# main.net
KiCad netlist of a schematic drawn in EAGLE
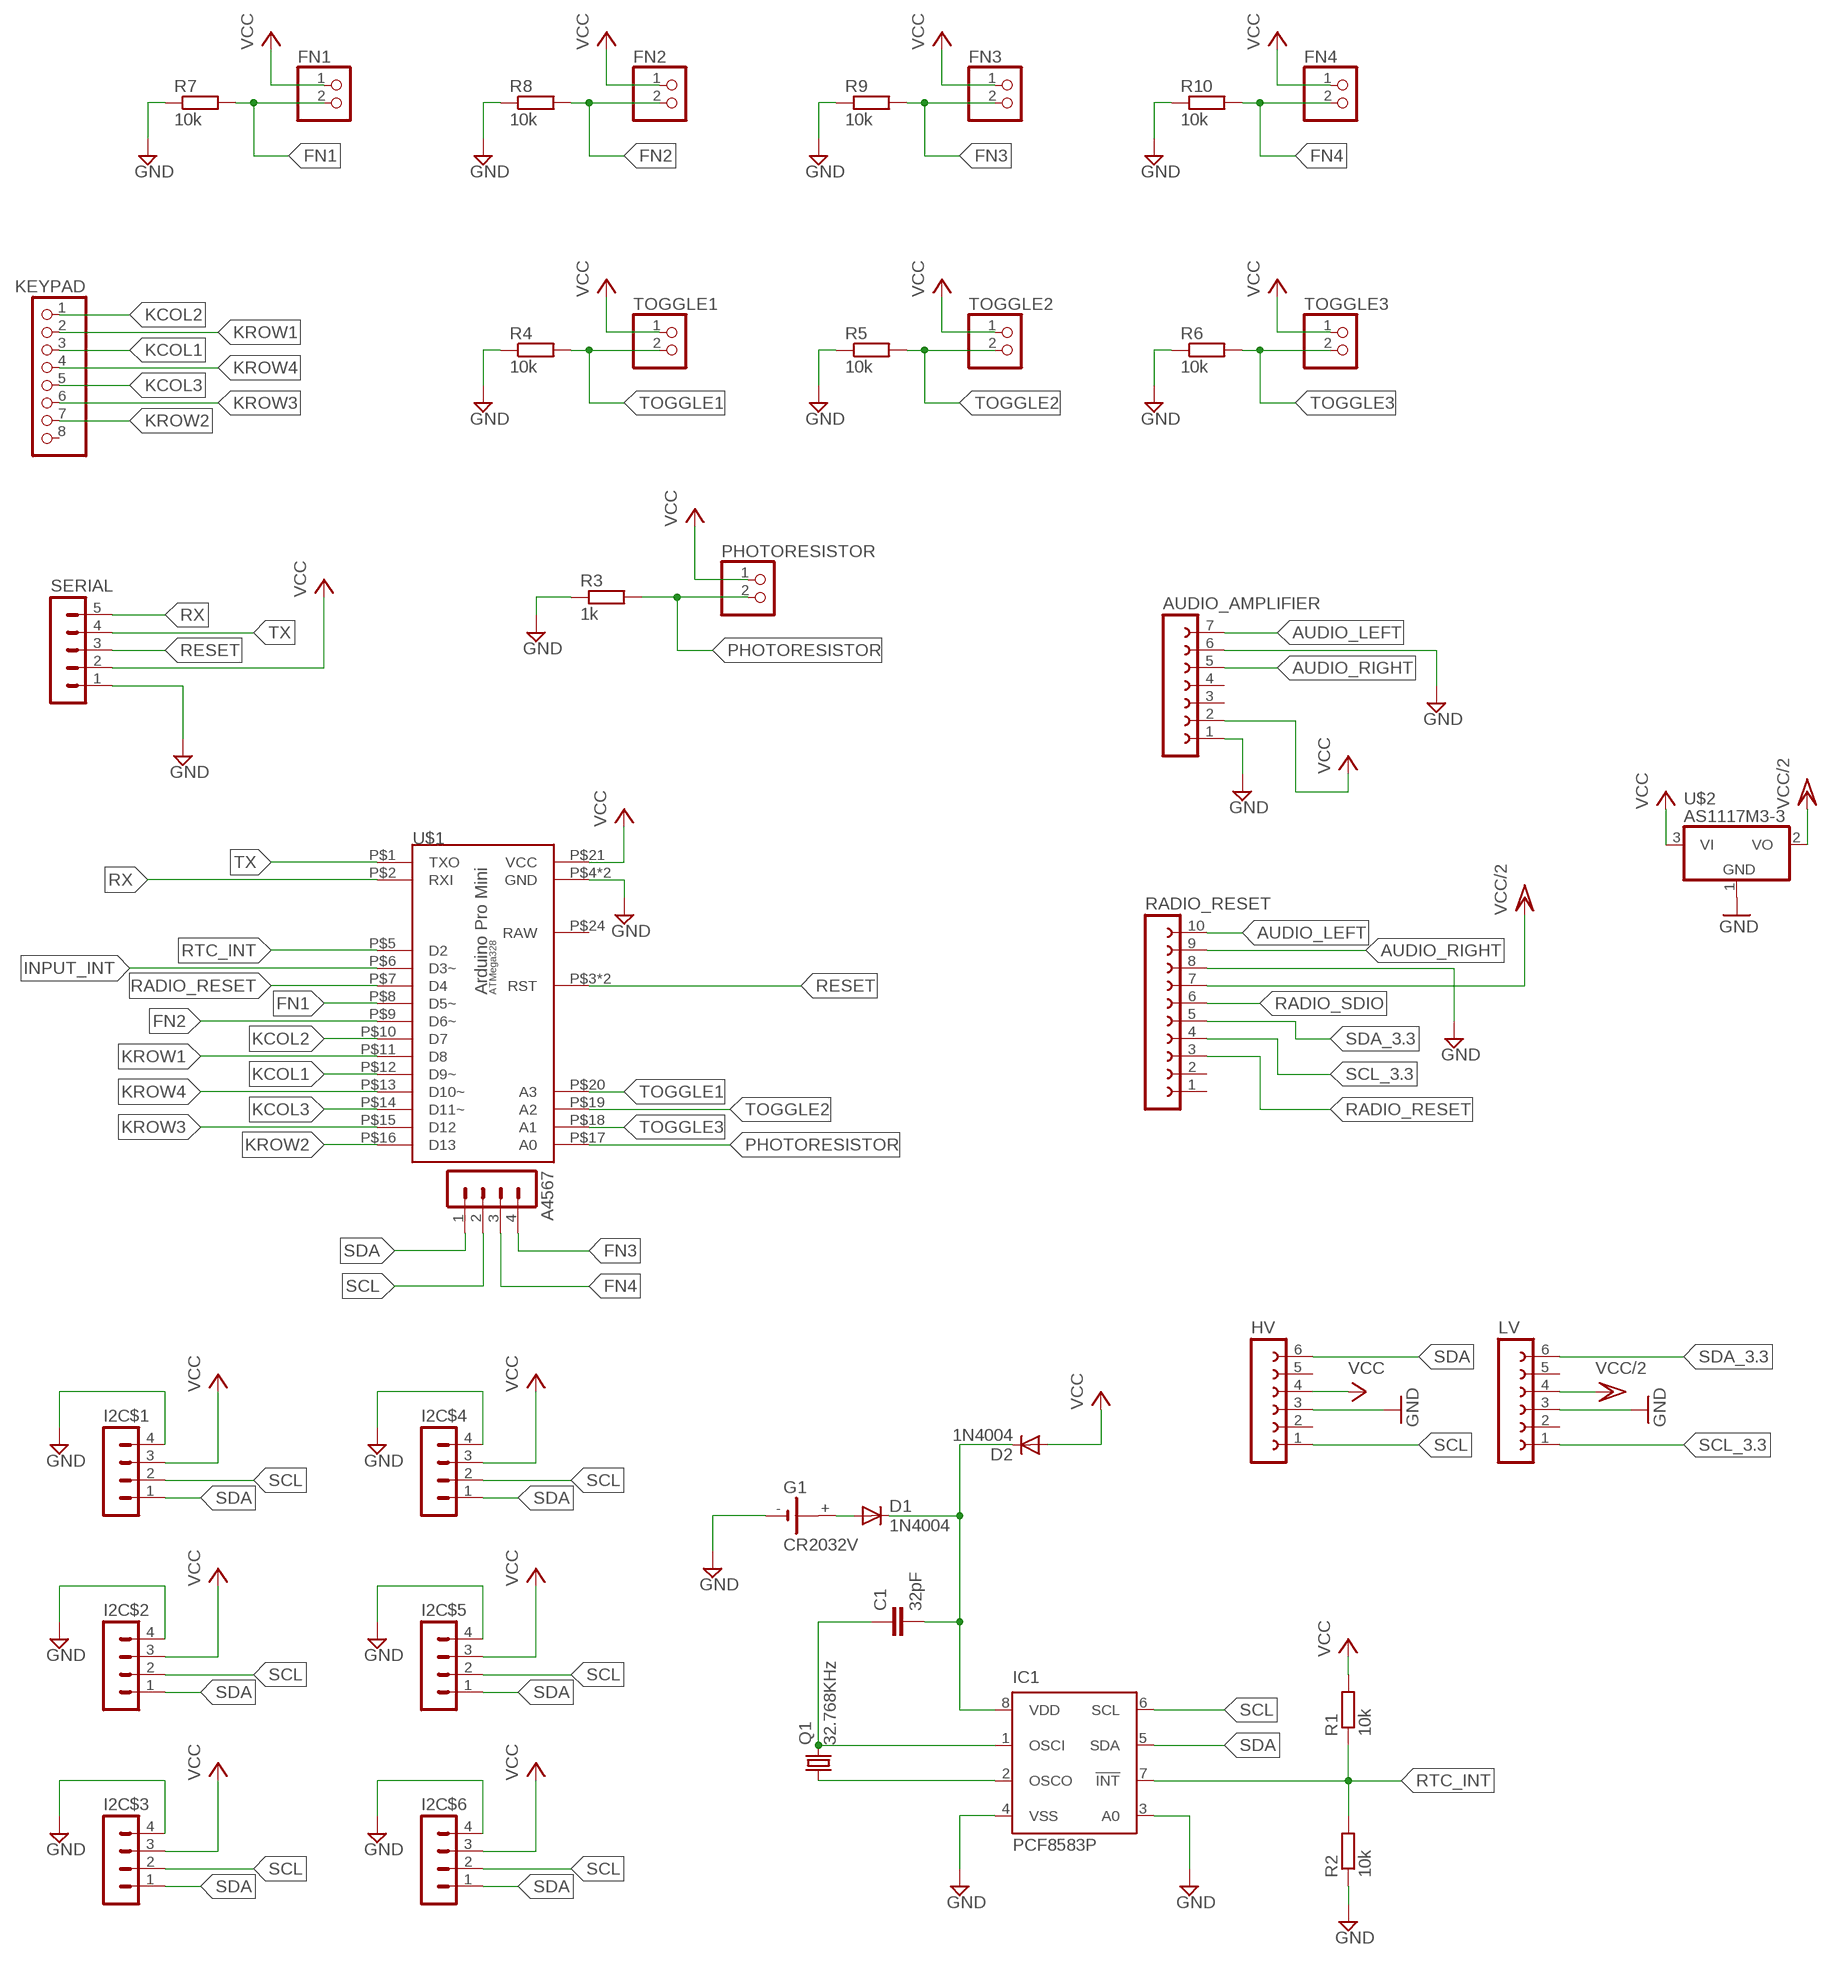
[diagram p0: schematic, sheet 1]

(export (version "E")
  (design (tool "Eeschema 10.0.6"))
  (components
    (comp (ref "A4567")
      (value "MA04-1")
      (footprint "eagle-import:MA04-1")
      (libsource (lib "eagle-import") (part "MA04-1"))
    )
    (comp (ref "AUDIO_AMPLIFIER")
      (value "FE07-1")
      (footprint "eagle-import:FE07")
      (libsource (lib "eagle-import") (part "FE07-1"))
    )
    (comp (ref "C1")
      (value "32pF")
      (footprint "eagle-import:C025-024X044")
      (libsource (lib "eagle-import") (part "C-EU025-024X044"))
    )
    (comp (ref "D1")
      (value "1N4004")
      (footprint "eagle-import:DO41-10")
      (libsource (lib "eagle-import") (part "1N4004"))
    )
    (comp (ref "D2")
      (value "1N4004")
      (footprint "eagle-import:DO41-10")
      (libsource (lib "eagle-import") (part "1N4004"))
    )
    (comp (ref "FN1")
      (value "PINHD-1X2")
      (footprint "eagle-import:1X02")
      (libsource (lib "eagle-import") (part "PINHD-1X2"))
    )
    (comp (ref "FN2")
      (value "PINHD-1X2")
      (footprint "eagle-import:1X02")
      (libsource (lib "eagle-import") (part "PINHD-1X2"))
    )
    (comp (ref "FN3")
      (value "PINHD-1X2")
      (footprint "eagle-import:1X02")
      (libsource (lib "eagle-import") (part "PINHD-1X2"))
    )
    (comp (ref "FN4")
      (value "PINHD-1X2")
      (footprint "eagle-import:1X02")
      (libsource (lib "eagle-import") (part "PINHD-1X2"))
    )
    (comp (ref "G1")
      (value "CR2032V")
      (footprint "eagle-import:CR2032V")
      (libsource (lib "eagle-import") (part "CR2032V"))
    )
    (comp (ref "HV")
      (value "FE06-1")
      (footprint "eagle-import:FE06")
      (libsource (lib "eagle-import") (part "FE06-1"))
    )
    (comp (ref "I2C$1")
      (value "MA04-1")
      (footprint "eagle-import:MA04-1")
      (libsource (lib "eagle-import") (part "MA04-1"))
    )
    (comp (ref "I2C$2")
      (value "MA04-1")
      (footprint "eagle-import:MA04-1")
      (libsource (lib "eagle-import") (part "MA04-1"))
    )
    (comp (ref "I2C$3")
      (value "MA04-1")
      (footprint "eagle-import:MA04-1")
      (libsource (lib "eagle-import") (part "MA04-1"))
    )
    (comp (ref "I2C$4")
      (value "MA04-1")
      (footprint "eagle-import:MA04-1")
      (libsource (lib "eagle-import") (part "MA04-1"))
    )
    (comp (ref "I2C$5")
      (value "MA04-1")
      (footprint "eagle-import:MA04-1")
      (libsource (lib "eagle-import") (part "MA04-1"))
    )
    (comp (ref "I2C$6")
      (value "MA04-1")
      (footprint "eagle-import:MA04-1")
      (libsource (lib "eagle-import") (part "MA04-1"))
    )
    (comp (ref "IC1")
      (value "PCF8583P")
      (footprint "eagle-import:DIL08")
      (libsource (lib "eagle-import") (part "PCF8583P"))
    )
    (comp (ref "KEYPAD")
      (value "PINHD-1X8")
      (footprint "eagle-import:1X08")
      (libsource (lib "eagle-import") (part "PINHD-1X8"))
    )
    (comp (ref "LV")
      (value "FE06-1")
      (footprint "eagle-import:FE06")
      (libsource (lib "eagle-import") (part "FE06-1"))
    )
    (comp (ref "PHOTORESISTOR")
      (value "PINHD-1X2")
      (footprint "eagle-import:1X02")
      (libsource (lib "eagle-import") (part "PINHD-1X2"))
    )
    (comp (ref "Q1")
      (value "32.768KHz")
      (footprint "eagle-import:TC26H")
      (libsource (lib "eagle-import") (part "CRYSTALTC26H"))
    )
    (comp (ref "R1")
      (value "10k")
      (footprint "eagle-import:M0805")
      (libsource (lib "eagle-import") (part "resistor_R-EU_M0805"))
    )
    (comp (ref "R2")
      (value "10k")
      (footprint "eagle-import:M0805")
      (libsource (lib "eagle-import") (part "resistor_R-EU_M0805"))
    )
    (comp (ref "R3")
      (value "1k")
      (footprint "eagle-import:M0805")
      (libsource (lib "eagle-import") (part "R-EU_M0805"))
    )
    (comp (ref "R4")
      (value "10k")
      (footprint "eagle-import:M0805")
      (libsource (lib "eagle-import") (part "resistor_R-EU_M0805"))
    )
    (comp (ref "R5")
      (value "10k")
      (footprint "eagle-import:M0805")
      (libsource (lib "eagle-import") (part "resistor_R-EU_M0805"))
    )
    (comp (ref "R6")
      (value "10k")
      (footprint "eagle-import:M0805")
      (libsource (lib "eagle-import") (part "resistor_R-EU_M0805"))
    )
    (comp (ref "R7")
      (value "10k")
      (footprint "eagle-import:M0805")
      (libsource (lib "eagle-import") (part "resistor_R-EU_M0805"))
    )
    (comp (ref "R8")
      (value "10k")
      (footprint "eagle-import:M0805")
      (libsource (lib "eagle-import") (part "resistor_R-EU_M0805"))
    )
    (comp (ref "R9")
      (value "10k")
      (footprint "eagle-import:M0805")
      (libsource (lib "eagle-import") (part "resistor_R-EU_M0805"))
    )
    (comp (ref "R10")
      (value "10k")
      (footprint "eagle-import:M0805")
      (libsource (lib "eagle-import") (part "resistor_R-EU_M0805"))
    )
    (comp (ref "RADIO_RESET")
      (value "FE10-1")
      (footprint "eagle-import:FE10")
      (libsource (lib "eagle-import") (part "FE10-1"))
    )
    (comp (ref "SERIAL")
      (value "MA05-1")
      (footprint "eagle-import:MA05-1")
      (libsource (lib "eagle-import") (part "MA05-1"))
    )
    (comp (ref "TOGGLE1")
      (value "PINHD-1X2")
      (footprint "eagle-import:1X02")
      (libsource (lib "eagle-import") (part "PINHD-1X2"))
    )
    (comp (ref "TOGGLE2")
      (value "PINHD-1X2")
      (footprint "eagle-import:1X02")
      (libsource (lib "eagle-import") (part "PINHD-1X2"))
    )
    (comp (ref "TOGGLE3")
      (value "PINHD-1X2")
      (footprint "eagle-import:1X02")
      (libsource (lib "eagle-import") (part "PINHD-1X2"))
    )
    (comp (ref "U$1")
      (value "ARDUINO-PRO-MINI-BARE")
      (footprint "eagle-import:DIP24W")
      (libsource (lib "eagle-import") (part "ARDUINO-PRO-MINI-BARE"))
    )
    (comp (ref "U$2")
      (value "AS1117M3-3")
      (footprint "eagle-import:SOT223")
      (libsource (lib "eagle-import") (part "AS1117M3-3"))
    )
  )
  (nets
    (net (code "1") (name "AUDIO_LEFT") (class "Default")
      (node (ref "AUDIO_AMPLIFIER") (pin "7") (pinfunction "7_7") (pintype "passive"))
      (node (ref "RADIO_RESET") (pin "10") (pinfunction "10_10") (pintype "passive"))
    )
    (net (code "2") (name "AUDIO_RIGHT") (class "Default")
      (node (ref "AUDIO_AMPLIFIER") (pin "5") (pinfunction "5_5") (pintype "passive"))
      (node (ref "RADIO_RESET") (pin "9") (pinfunction "9_9") (pintype "passive"))
    )
    (net (code "3") (name "FN1") (class "Default")
      (node (ref "FN1") (pin "2") (pinfunction "2_2") (pintype "passive"))
      (node (ref "R7") (pin "2") (pinfunction "2_2") (pintype "passive"))
      (node (ref "U$1") (pin "P$8") (pinfunction "D5~{}_P$8") (pintype "bidirectional"))
    )
    (net (code "4") (name "FN2") (class "Default")
      (node (ref "FN2") (pin "2") (pinfunction "2_2") (pintype "passive"))
      (node (ref "R8") (pin "2") (pinfunction "2_2") (pintype "passive"))
      (node (ref "U$1") (pin "P$9") (pinfunction "D6~{}_P$9") (pintype "bidirectional"))
    )
    (net (code "5") (name "FN3") (class "Default")
      (node (ref "A4567") (pin "4") (pinfunction "4_4") (pintype "passive"))
      (node (ref "FN3") (pin "2") (pinfunction "2_2") (pintype "passive"))
      (node (ref "R9") (pin "2") (pinfunction "2_2") (pintype "passive"))
    )
    (net (code "6") (name "FN4") (class "Default")
      (node (ref "A4567") (pin "3") (pinfunction "3_3") (pintype "passive"))
      (node (ref "FN4") (pin "2") (pinfunction "2_2") (pintype "passive"))
      (node (ref "R10") (pin "2") (pinfunction "2_2") (pintype "passive"))
    )
    (net (code "7") (name "GND") (class "Default")
      (node (ref "AUDIO_AMPLIFIER") (pin "1") (pinfunction "1_1") (pintype "passive"))
      (node (ref "AUDIO_AMPLIFIER") (pin "6") (pinfunction "6_6") (pintype "passive"))
      (node (ref "G1") (pin "-") (pinfunction "-_-") (pintype "passive"))
      (node (ref "HV") (pin "3") (pinfunction "3_3") (pintype "passive"))
      (node (ref "I2C$1") (pin "4") (pinfunction "4_4") (pintype "passive"))
      (node (ref "I2C$2") (pin "4") (pinfunction "4_4") (pintype "passive"))
      (node (ref "I2C$3") (pin "4") (pinfunction "4_4") (pintype "passive"))
      (node (ref "I2C$4") (pin "4") (pinfunction "4_4") (pintype "passive"))
      (node (ref "I2C$5") (pin "4") (pinfunction "4_4") (pintype "passive"))
      (node (ref "I2C$6") (pin "4") (pinfunction "4_4") (pintype "passive"))
      (node (ref "IC1") (pin "3") (pinfunction "A0_3") (pintype "input"))
      (node (ref "IC1") (pin "4") (pinfunction "VSS_4") (pintype "power_in"))
      (node (ref "LV") (pin "3") (pinfunction "3_3") (pintype "passive"))
      (node (ref "R10") (pin "1") (pinfunction "1_1") (pintype "passive"))
      (node (ref "R2") (pin "1") (pinfunction "1_1") (pintype "passive"))
      (node (ref "R3") (pin "1") (pinfunction "1_1") (pintype "passive"))
      (node (ref "R4") (pin "1") (pinfunction "1_1") (pintype "passive"))
      (node (ref "R5") (pin "1") (pinfunction "1_1") (pintype "passive"))
      (node (ref "R6") (pin "1") (pinfunction "1_1") (pintype "passive"))
      (node (ref "R7") (pin "1") (pinfunction "1_1") (pintype "passive"))
      (node (ref "R8") (pin "1") (pinfunction "1_1") (pintype "passive"))
      (node (ref "R9") (pin "1") (pinfunction "1_1") (pintype "passive"))
      (node (ref "RADIO_RESET") (pin "8") (pinfunction "8_8") (pintype "passive"))
      (node (ref "SERIAL") (pin "1") (pinfunction "1_1") (pintype "passive"))
      (node (ref "U$1") (pin "P$23") (pinfunction "GND_P$23") (pintype "bidirectional"))
      (node (ref "U$1") (pin "P$4") (pinfunction "GND_P$4") (pintype "bidirectional"))
      (node (ref "U$2") (pin "1") (pinfunction "GND_1") (pintype "passive"))
    )
    (net (code "8") (name "INPUT_INT") (class "Default")
      (node (ref "U$1") (pin "P$6") (pinfunction "D3~{}_P$6") (pintype "bidirectional"))
    )
    (net (code "9") (name "KCOL1") (class "Default")
      (node (ref "KEYPAD") (pin "3") (pinfunction "3_3") (pintype "passive"))
      (node (ref "U$1") (pin "P$12") (pinfunction "D9~{}_P$12") (pintype "bidirectional"))
    )
    (net (code "10") (name "KCOL2") (class "Default")
      (node (ref "KEYPAD") (pin "1") (pinfunction "1_1") (pintype "passive"))
      (node (ref "U$1") (pin "P$10") (pinfunction "D7_P$10") (pintype "bidirectional"))
    )
    (net (code "11") (name "KCOL3") (class "Default")
      (node (ref "KEYPAD") (pin "5") (pinfunction "5_5") (pintype "passive"))
      (node (ref "U$1") (pin "P$14") (pinfunction "D11~{}_P$14") (pintype "bidirectional"))
    )
    (net (code "12") (name "KROW1") (class "Default")
      (node (ref "KEYPAD") (pin "2") (pinfunction "2_2") (pintype "passive"))
      (node (ref "U$1") (pin "P$11") (pinfunction "D8_P$11") (pintype "bidirectional"))
    )
    (net (code "13") (name "KROW2") (class "Default")
      (node (ref "KEYPAD") (pin "7") (pinfunction "7_7") (pintype "passive"))
      (node (ref "U$1") (pin "P$16") (pinfunction "D13_P$16") (pintype "bidirectional"))
    )
    (net (code "14") (name "KROW3") (class "Default")
      (node (ref "KEYPAD") (pin "6") (pinfunction "6_6") (pintype "passive"))
      (node (ref "U$1") (pin "P$15") (pinfunction "D12_P$15") (pintype "bidirectional"))
    )
    (net (code "15") (name "KROW4") (class "Default")
      (node (ref "KEYPAD") (pin "4") (pinfunction "4_4") (pintype "passive"))
      (node (ref "U$1") (pin "P$13") (pinfunction "D10~{}_P$13") (pintype "bidirectional"))
    )
    (net (code "16") (name "Net-(D1-PadA)") (class "Default")
      (node (ref "D1") (pin "A") (pinfunction "A_A") (pintype "passive"))
      (node (ref "G1") (pin "+") (pinfunction "+_+") (pintype "passive"))
    )
    (net (code "17") (name "Net-(IC1-OSCI)") (class "Default")
      (node (ref "C1") (pin "1") (pinfunction "1_1") (pintype "passive"))
      (node (ref "IC1") (pin "1") (pinfunction "OSCI_1") (pintype "input"))
      (node (ref "Q1") (pin "2") (pinfunction "2_2") (pintype "passive"))
    )
    (net (code "18") (name "Net-(IC1-OSCO)") (class "Default")
      (node (ref "IC1") (pin "2") (pinfunction "OSCO_2") (pintype "output"))
      (node (ref "Q1") (pin "1") (pinfunction "1_1") (pintype "passive"))
    )
    (net (code "19") (name "Net-(IC1-VDD)") (class "Default")
      (node (ref "C1") (pin "2") (pinfunction "2_2") (pintype "passive"))
      (node (ref "D1") (pin "C") (pinfunction "C_C") (pintype "passive"))
      (node (ref "D2") (pin "C") (pinfunction "C_C") (pintype "passive"))
      (node (ref "IC1") (pin "8") (pinfunction "VDD_8") (pintype "power_in"))
    )
    (net (code "20") (name "PHOTORESISTOR") (class "Default")
      (node (ref "PHOTORESISTOR") (pin "2") (pinfunction "2_2") (pintype "passive"))
      (node (ref "R3") (pin "2") (pinfunction "2_2") (pintype "passive"))
      (node (ref "U$1") (pin "P$17") (pinfunction "A0_P$17") (pintype "bidirectional"))
    )
    (net (code "21") (name "RADIO_RESET") (class "Default")
      (node (ref "RADIO_RESET") (pin "3") (pinfunction "3_3") (pintype "passive"))
      (node (ref "U$1") (pin "P$7") (pinfunction "D4_P$7") (pintype "bidirectional"))
    )
    (net (code "22") (name "RADIO_SDIO") (class "Default")
      (node (ref "RADIO_RESET") (pin "6") (pinfunction "6_6") (pintype "passive"))
    )
    (net (code "23") (name "RESET") (class "Default")
      (node (ref "SERIAL") (pin "3") (pinfunction "3_3") (pintype "passive"))
      (node (ref "U$1") (pin "P$22") (pinfunction "RST_P$22") (pintype "bidirectional"))
      (node (ref "U$1") (pin "P$3") (pinfunction "RST_P$3") (pintype "bidirectional"))
    )
    (net (code "24") (name "RTC_INT") (class "Default")
      (node (ref "IC1") (pin "7") (pinfunction "~{INT}_7") (pintype "open_collector"))
      (node (ref "R1") (pin "1") (pinfunction "1_1") (pintype "passive"))
      (node (ref "R2") (pin "2") (pinfunction "2_2") (pintype "passive"))
      (node (ref "U$1") (pin "P$5") (pinfunction "D2_P$5") (pintype "bidirectional"))
    )
    (net (code "25") (name "RX") (class "Default")
      (node (ref "SERIAL") (pin "5") (pinfunction "5_5") (pintype "passive"))
      (node (ref "U$1") (pin "P$2") (pinfunction "RXI_P$2") (pintype "input"))
    )
    (net (code "26") (name "SCL") (class "Default")
      (node (ref "A4567") (pin "2") (pinfunction "2_2") (pintype "passive"))
      (node (ref "HV") (pin "1") (pinfunction "1_1") (pintype "passive"))
      (node (ref "I2C$1") (pin "2") (pinfunction "2_2") (pintype "passive"))
      (node (ref "I2C$2") (pin "2") (pinfunction "2_2") (pintype "passive"))
      (node (ref "I2C$3") (pin "2") (pinfunction "2_2") (pintype "passive"))
      (node (ref "I2C$4") (pin "2") (pinfunction "2_2") (pintype "passive"))
      (node (ref "I2C$5") (pin "2") (pinfunction "2_2") (pintype "passive"))
      (node (ref "I2C$6") (pin "2") (pinfunction "2_2") (pintype "passive"))
      (node (ref "IC1") (pin "6") (pinfunction "SCL_6") (pintype "input"))
    )
    (net (code "27") (name "SCL_3.3") (class "Default")
      (node (ref "LV") (pin "1") (pinfunction "1_1") (pintype "passive"))
      (node (ref "RADIO_RESET") (pin "4") (pinfunction "4_4") (pintype "passive"))
    )
    (net (code "28") (name "SDA") (class "Default")
      (node (ref "A4567") (pin "1") (pinfunction "1_1") (pintype "passive"))
      (node (ref "HV") (pin "6") (pinfunction "6_6") (pintype "passive"))
      (node (ref "I2C$1") (pin "1") (pinfunction "1_1") (pintype "passive"))
      (node (ref "I2C$2") (pin "1") (pinfunction "1_1") (pintype "passive"))
      (node (ref "I2C$3") (pin "1") (pinfunction "1_1") (pintype "passive"))
      (node (ref "I2C$4") (pin "1") (pinfunction "1_1") (pintype "passive"))
      (node (ref "I2C$5") (pin "1") (pinfunction "1_1") (pintype "passive"))
      (node (ref "I2C$6") (pin "1") (pinfunction "1_1") (pintype "passive"))
      (node (ref "IC1") (pin "5") (pinfunction "SDA_5") (pintype "bidirectional"))
    )
    (net (code "29") (name "SDA_3.3") (class "Default")
      (node (ref "LV") (pin "6") (pinfunction "6_6") (pintype "passive"))
      (node (ref "RADIO_RESET") (pin "5") (pinfunction "5_5") (pintype "passive"))
    )
    (net (code "30") (name "TOGGLE1") (class "Default")
      (node (ref "R4") (pin "2") (pinfunction "2_2") (pintype "passive"))
      (node (ref "TOGGLE1") (pin "2") (pinfunction "2_2") (pintype "passive"))
      (node (ref "U$1") (pin "P$20") (pinfunction "A3_P$20") (pintype "bidirectional"))
    )
    (net (code "31") (name "TOGGLE2") (class "Default")
      (node (ref "R5") (pin "2") (pinfunction "2_2") (pintype "passive"))
      (node (ref "TOGGLE2") (pin "2") (pinfunction "2_2") (pintype "passive"))
      (node (ref "U$1") (pin "P$19") (pinfunction "A2_P$19") (pintype "bidirectional"))
    )
    (net (code "32") (name "TOGGLE3") (class "Default")
      (node (ref "R6") (pin "2") (pinfunction "2_2") (pintype "passive"))
      (node (ref "TOGGLE3") (pin "2") (pinfunction "2_2") (pintype "passive"))
      (node (ref "U$1") (pin "P$18") (pinfunction "A1_P$18") (pintype "bidirectional"))
    )
    (net (code "33") (name "TX") (class "Default")
      (node (ref "SERIAL") (pin "4") (pinfunction "4_4") (pintype "passive"))
      (node (ref "U$1") (pin "P$1") (pinfunction "TXO_P$1") (pintype "bidirectional"))
    )
    (net (code "34") (name "VCC") (class "Default")
      (node (ref "AUDIO_AMPLIFIER") (pin "2") (pinfunction "2_2") (pintype "passive"))
      (node (ref "D2") (pin "A") (pinfunction "A_A") (pintype "passive"))
      (node (ref "FN1") (pin "1") (pinfunction "1_1") (pintype "passive"))
      (node (ref "FN2") (pin "1") (pinfunction "1_1") (pintype "passive"))
      (node (ref "FN3") (pin "1") (pinfunction "1_1") (pintype "passive"))
      (node (ref "FN4") (pin "1") (pinfunction "1_1") (pintype "passive"))
      (node (ref "HV") (pin "4") (pinfunction "4_4") (pintype "passive"))
      (node (ref "I2C$1") (pin "3") (pinfunction "3_3") (pintype "passive"))
      (node (ref "I2C$2") (pin "3") (pinfunction "3_3") (pintype "passive"))
      (node (ref "I2C$3") (pin "3") (pinfunction "3_3") (pintype "passive"))
      (node (ref "I2C$4") (pin "3") (pinfunction "3_3") (pintype "passive"))
      (node (ref "I2C$5") (pin "3") (pinfunction "3_3") (pintype "passive"))
      (node (ref "I2C$6") (pin "3") (pinfunction "3_3") (pintype "passive"))
      (node (ref "PHOTORESISTOR") (pin "1") (pinfunction "1_1") (pintype "passive"))
      (node (ref "R1") (pin "2") (pinfunction "2_2") (pintype "passive"))
      (node (ref "SERIAL") (pin "2") (pinfunction "2_2") (pintype "passive"))
      (node (ref "TOGGLE1") (pin "1") (pinfunction "1_1") (pintype "passive"))
      (node (ref "TOGGLE2") (pin "1") (pinfunction "1_1") (pintype "passive"))
      (node (ref "TOGGLE3") (pin "1") (pinfunction "1_1") (pintype "passive"))
      (node (ref "U$1") (pin "P$21") (pinfunction "VCC_P$21") (pintype "bidirectional"))
      (node (ref "U$2") (pin "3") (pinfunction "VI_3") (pintype "input"))
    )
    (net (code "35") (name "VCC{slash}2") (class "Default")
      (node (ref "LV") (pin "4") (pinfunction "4_4") (pintype "passive"))
      (node (ref "RADIO_RESET") (pin "7") (pinfunction "7_7") (pintype "passive"))
      (node (ref "U$2") (pin "2") (pinfunction "VO_2") (pintype "passive"))
    )
    (net (code "36") (name "unconnected-(AUDIO_AMPLIFIER-Pad3)") (class "Default")
      (node (ref "AUDIO_AMPLIFIER") (pin "3") (pinfunction "3_3") (pintype "passive"))
    )
    (net (code "37") (name "unconnected-(AUDIO_AMPLIFIER-Pad4)") (class "Default")
      (node (ref "AUDIO_AMPLIFIER") (pin "4") (pinfunction "4_4") (pintype "passive"))
    )
    (net (code "38") (name "unconnected-(G1-+-Pad+@1)") (class "Default")
      (node (ref "G1") (pin "+@1") (pinfunction "+_+@1") (pintype "passive"))
    )
    (net (code "39") (name "unconnected-(HV-Pad2)") (class "Default")
      (node (ref "HV") (pin "2") (pinfunction "2_2") (pintype "passive"))
    )
    (net (code "40") (name "unconnected-(HV-Pad5)") (class "Default")
      (node (ref "HV") (pin "5") (pinfunction "5_5") (pintype "passive"))
    )
    (net (code "41") (name "unconnected-(KEYPAD-Pad8)") (class "Default")
      (node (ref "KEYPAD") (pin "8") (pinfunction "8_8") (pintype "passive"))
    )
    (net (code "42") (name "unconnected-(LV-Pad2)") (class "Default")
      (node (ref "LV") (pin "2") (pinfunction "2_2") (pintype "passive"))
    )
    (net (code "43") (name "unconnected-(LV-Pad5)") (class "Default")
      (node (ref "LV") (pin "5") (pinfunction "5_5") (pintype "passive"))
    )
    (net (code "44") (name "unconnected-(RADIO_RESET-Pad1)") (class "Default")
      (node (ref "RADIO_RESET") (pin "1") (pinfunction "1_1") (pintype "passive"))
    )
    (net (code "45") (name "unconnected-(RADIO_RESET-Pad2)") (class "Default")
      (node (ref "RADIO_RESET") (pin "2") (pinfunction "2_2") (pintype "passive"))
    )
    (net (code "46") (name "unconnected-(U$1-RAW-PadP$24)") (class "Default")
      (node (ref "U$1") (pin "P$24") (pinfunction "RAW_P$24") (pintype "bidirectional"))
    )
  )
)
